# loom-side-panel-left.net
KiCad netlist of a schematic drawn in Altium Designer
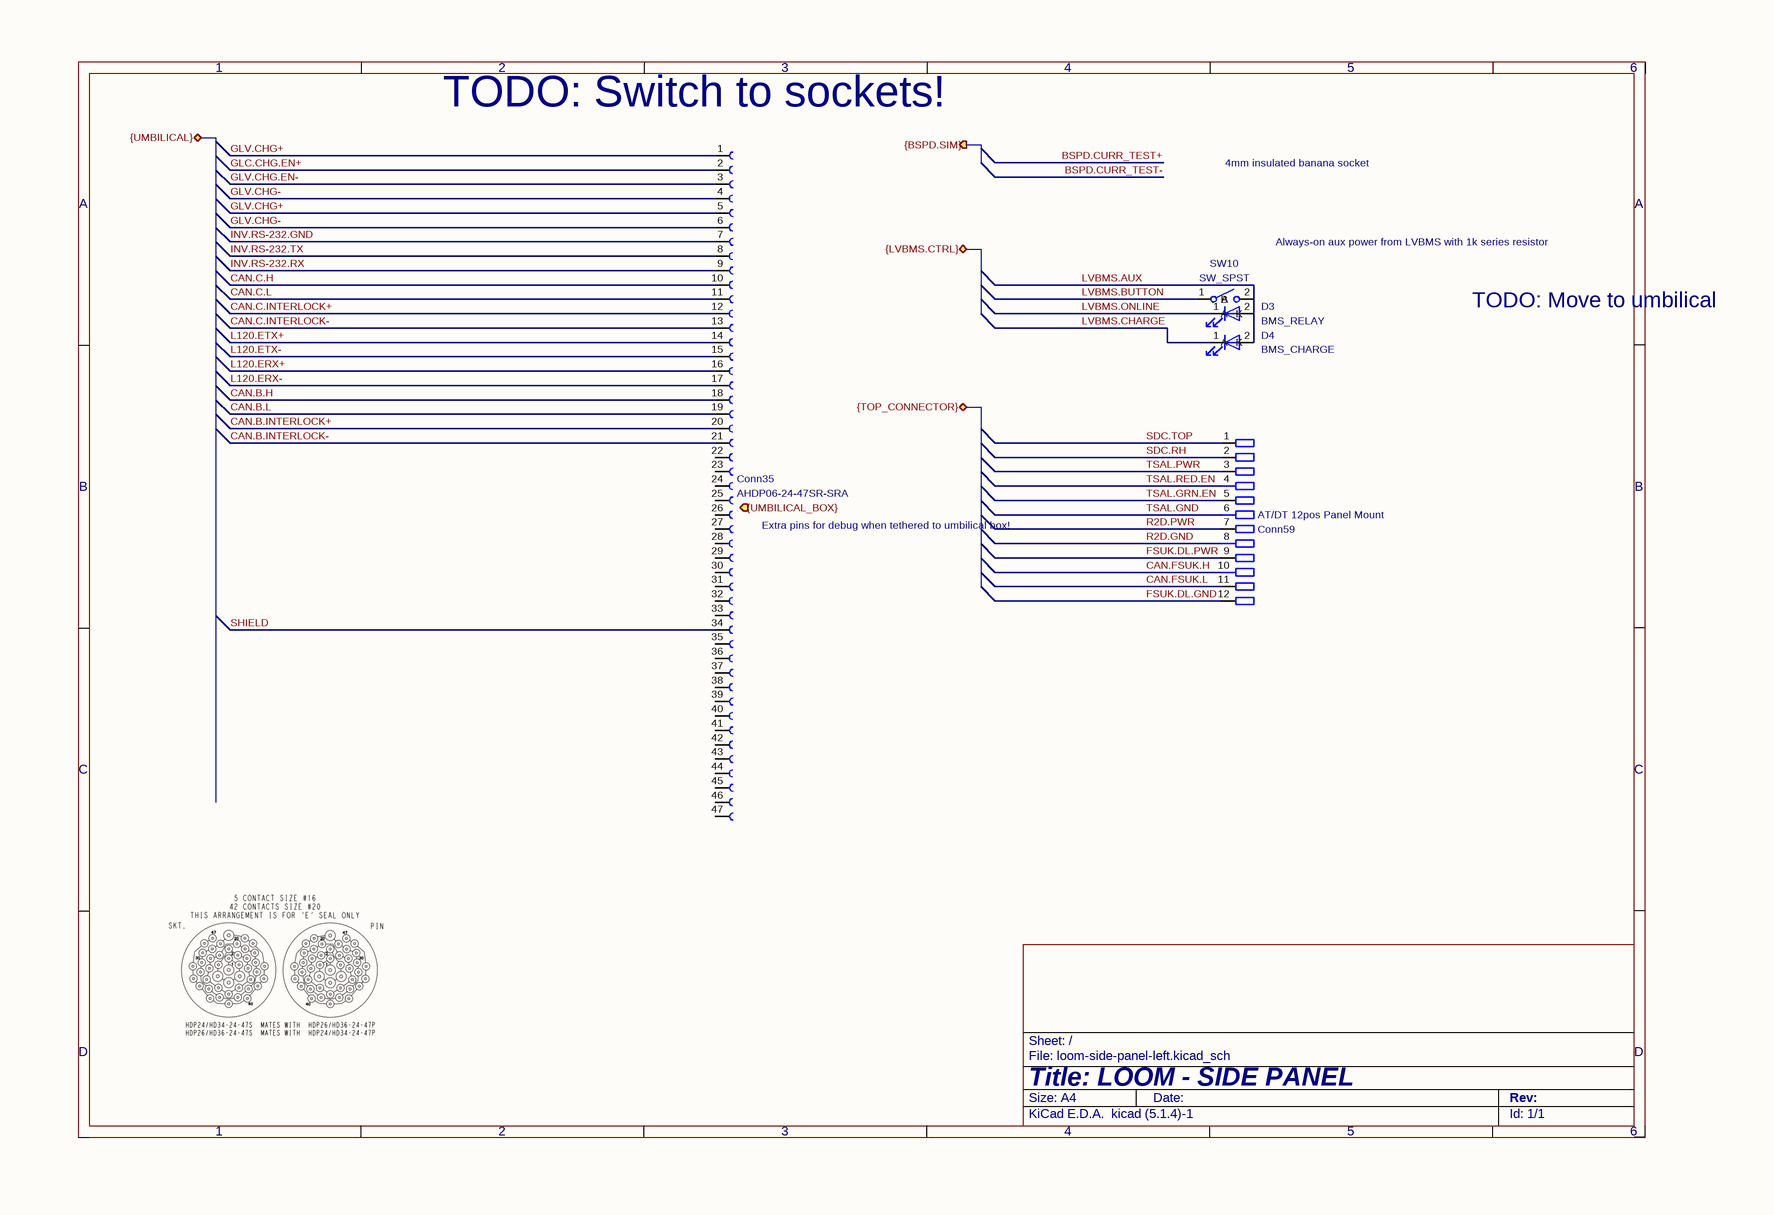
[diagram p0: loom-side-panel-left.SchDoc]

(export (version "E")
  (design (tool "Eeschema 10.0.6"))
  (components
    (comp (ref "Conn35")
      (value "AMPHENOL-47P-Recepticle")
      (fields (field (name "P/N") "AHDP06-24-47SR-SRA"))
      (libsource (lib "Connectors_SUFST") (part "AMPHENOL-47P-Recepticle"))
    )
    (comp (ref "Conn59")
      (value "AMPHENOL-21P-Pannel")
      (fields (field (name "P/N") "AT/DT 12pos Panel Mount"))
      (libsource (lib "Connectors_SUFST") (part "Deutsch_DTM_12P_Pin"))
    )
    (comp (ref "D3")
      (value "BMS_RELAY")
      (description "Light emitting diode")
      (libsource (lib "Device") (part "LED"))
    )
    (comp (ref "D4")
      (value "BMS_CHARGE")
      (description "Light emitting diode")
      (libsource (lib "Device") (part "LED"))
    )
    (comp (ref "SW10")
      (value "SW_SPST")
      (description "Single Pole Single Throw (SPST) switch")
      (libsource (lib "Switch") (part "SW_SPST"))
    )
  )
  (nets
    (net (code "8") (name "/CAN.B.H") (class "Default")
      (node (ref "Conn35") (pin "18") (pinfunction "18_18") (pintype "passive"))
    )
    (net (code "9") (name "/CAN.B.INTERLOCK+") (class "Default")
      (node (ref "Conn35") (pin "20") (pinfunction "20_20") (pintype "passive"))
    )
    (net (code "10") (name "/CAN.B.INTERLOCK-") (class "Default")
      (node (ref "Conn35") (pin "21") (pinfunction "21_21") (pintype "passive"))
    )
    (net (code "11") (name "/CAN.B.L") (class "Default")
      (node (ref "Conn35") (pin "19") (pinfunction "19_19") (pintype "passive"))
    )
    (net (code "12") (name "/CAN.C.H") (class "Default")
      (node (ref "Conn35") (pin "10") (pinfunction "10_10") (pintype "passive"))
    )
    (net (code "13") (name "/CAN.C.INTERLOCK+") (class "Default")
      (node (ref "Conn35") (pin "12") (pinfunction "12_12") (pintype "passive"))
    )
    (net (code "14") (name "/CAN.C.INTERLOCK-") (class "Default")
      (node (ref "Conn35") (pin "13") (pinfunction "13_13") (pintype "passive"))
    )
    (net (code "15") (name "/CAN.C.L") (class "Default")
      (node (ref "Conn35") (pin "11") (pinfunction "11_11") (pintype "passive"))
    )
    (net (code "16") (name "/CAN.FSUK.H") (class "Default")
      (node (ref "Conn59") (pin "10") (pinfunction "10_10") (pintype "passive"))
    )
    (net (code "17") (name "/CAN.FSUK.L") (class "Default")
      (node (ref "Conn59") (pin "11") (pinfunction "11_11") (pintype "passive"))
    )
    (net (code "18") (name "/FSUK.DL.GND") (class "Default")
      (node (ref "Conn59") (pin "12") (pinfunction "12_12") (pintype "passive"))
    )
    (net (code "19") (name "/FSUK.DL.PWR") (class "Default")
      (node (ref "Conn59") (pin "9") (pinfunction "9_9") (pintype "passive"))
    )
    (net (code "20") (name "/GLC.CHG.EN+") (class "Default")
      (node (ref "Conn35") (pin "2") (pinfunction "2_2") (pintype "passive"))
    )
    (net (code "21") (name "/GLV.CHG+") (class "Default")
      (node (ref "Conn35") (pin "1") (pinfunction "1_1") (pintype "passive"))
      (node (ref "Conn35") (pin "5") (pinfunction "5_5") (pintype "passive"))
    )
    (net (code "22") (name "/GLV.CHG-") (class "Default")
      (node (ref "Conn35") (pin "4") (pinfunction "4_4") (pintype "passive"))
      (node (ref "Conn35") (pin "6") (pinfunction "6_6") (pintype "passive"))
    )
    (net (code "23") (name "/GLV.CHG.EN-") (class "Default")
      (node (ref "Conn35") (pin "3") (pinfunction "3_3") (pintype "passive"))
    )
    (net (code "24") (name "/INV.RS-232.GND") (class "Default")
      (node (ref "Conn35") (pin "7") (pinfunction "7_7") (pintype "passive"))
    )
    (net (code "25") (name "/INV.RS-232.RX") (class "Default")
      (node (ref "Conn35") (pin "9") (pinfunction "9_9") (pintype "passive"))
    )
    (net (code "26") (name "/INV.RS-232.TX") (class "Default")
      (node (ref "Conn35") (pin "8") (pinfunction "8_8") (pintype "passive"))
    )
    (net (code "27") (name "/L120.ERX+") (class "Default")
      (node (ref "Conn35") (pin "16") (pinfunction "16_16") (pintype "passive"))
    )
    (net (code "28") (name "/L120.ERX-") (class "Default")
      (node (ref "Conn35") (pin "17") (pinfunction "17_17") (pintype "passive"))
    )
    (net (code "29") (name "/L120.ETX+") (class "Default")
      (node (ref "Conn35") (pin "14") (pinfunction "14_14") (pintype "passive"))
    )
    (net (code "30") (name "/L120.ETX-") (class "Default")
      (node (ref "Conn35") (pin "15") (pinfunction "15_15") (pintype "passive"))
    )
    (net (code "31") (name "/LVBMS.AUX") (class "Default")
      (node (ref "D3") (pin "2") (pinfunction "A_2") (pintype "passive"))
      (node (ref "D4") (pin "2") (pinfunction "A_2") (pintype "passive"))
      (node (ref "SW10") (pin "2") (pinfunction "B_2") (pintype "passive"))
    )
    (net (code "32") (name "/LVBMS.BUTTON") (class "Default")
      (node (ref "SW10") (pin "1") (pinfunction "A_1") (pintype "passive"))
    )
    (net (code "33") (name "/LVBMS.CHARGE") (class "Default")
      (node (ref "D4") (pin "1") (pinfunction "K_1") (pintype "passive"))
    )
    (net (code "34") (name "/LVBMS.ONLINE") (class "Default")
      (node (ref "D3") (pin "1") (pinfunction "K_1") (pintype "passive"))
    )
    (net (code "35") (name "/R2D.GND") (class "Default")
      (node (ref "Conn59") (pin "8") (pinfunction "8_8") (pintype "passive"))
    )
    (net (code "36") (name "/R2D.PWR") (class "Default")
      (node (ref "Conn59") (pin "7") (pinfunction "7_7") (pintype "passive"))
    )
    (net (code "37") (name "/SDC.RH") (class "Default")
      (node (ref "Conn59") (pin "2") (pinfunction "2_2") (pintype "passive"))
    )
    (net (code "38") (name "/SDC.TOP") (class "Default")
      (node (ref "Conn59") (pin "1") (pinfunction "1_1") (pintype "passive"))
    )
    (net (code "39") (name "/SHIELD") (class "Default")
      (node (ref "Conn35") (pin "34") (pinfunction "34_34") (pintype "passive"))
    )
    (net (code "40") (name "/TSAL.GND") (class "Default")
      (node (ref "Conn59") (pin "6") (pinfunction "6_6") (pintype "passive"))
    )
    (net (code "41") (name "/TSAL.GRN.EN") (class "Default")
      (node (ref "Conn59") (pin "5") (pinfunction "5_5") (pintype "passive"))
    )
    (net (code "42") (name "/TSAL.PWR") (class "Default")
      (node (ref "Conn59") (pin "3") (pinfunction "3_3") (pintype "passive"))
    )
    (net (code "43") (name "/TSAL.RED.EN") (class "Default")
      (node (ref "Conn59") (pin "4") (pinfunction "4_4") (pintype "passive"))
    )
    (net (code "49") (name "unconnected-(Conn35-Pad22)") (class "Default")
      (node (ref "Conn35") (pin "22") (pinfunction "22_22") (pintype "passive"))
    )
    (net (code "50") (name "unconnected-(Conn35-Pad23)") (class "Default")
      (node (ref "Conn35") (pin "23") (pinfunction "23_23") (pintype "passive"))
    )
    (net (code "51") (name "unconnected-(Conn35-Pad24)") (class "Default")
      (node (ref "Conn35") (pin "24") (pinfunction "24_24") (pintype "passive"))
    )
    (net (code "52") (name "unconnected-(Conn35-Pad25)") (class "Default")
      (node (ref "Conn35") (pin "25") (pinfunction "25_25") (pintype "passive"))
    )
    (net (code "53") (name "unconnected-(Conn35-Pad26)") (class "Default")
      (node (ref "Conn35") (pin "26") (pinfunction "26_26") (pintype "passive"))
    )
    (net (code "54") (name "unconnected-(Conn35-Pad27)") (class "Default")
      (node (ref "Conn35") (pin "27") (pinfunction "27_27") (pintype "passive"))
    )
    (net (code "55") (name "unconnected-(Conn35-Pad28)") (class "Default")
      (node (ref "Conn35") (pin "28") (pinfunction "28_28") (pintype "passive"))
    )
    (net (code "56") (name "unconnected-(Conn35-Pad29)") (class "Default")
      (node (ref "Conn35") (pin "29") (pinfunction "29_29") (pintype "passive"))
    )
    (net (code "57") (name "unconnected-(Conn35-Pad30)") (class "Default")
      (node (ref "Conn35") (pin "30") (pinfunction "30_30") (pintype "passive"))
    )
    (net (code "58") (name "unconnected-(Conn35-Pad31)") (class "Default")
      (node (ref "Conn35") (pin "31") (pinfunction "31_31") (pintype "passive"))
    )
    (net (code "59") (name "unconnected-(Conn35-Pad32)") (class "Default")
      (node (ref "Conn35") (pin "32") (pinfunction "32_32") (pintype "passive"))
    )
    (net (code "60") (name "unconnected-(Conn35-Pad33)") (class "Default")
      (node (ref "Conn35") (pin "33") (pinfunction "33_33") (pintype "passive"))
    )
    (net (code "61") (name "unconnected-(Conn35-Pad35)") (class "Default")
      (node (ref "Conn35") (pin "35") (pinfunction "35_35") (pintype "passive"))
    )
    (net (code "62") (name "unconnected-(Conn35-Pad36)") (class "Default")
      (node (ref "Conn35") (pin "36") (pinfunction "36_36") (pintype "passive"))
    )
    (net (code "63") (name "unconnected-(Conn35-Pad37)") (class "Default")
      (node (ref "Conn35") (pin "37") (pinfunction "37_37") (pintype "passive"))
    )
    (net (code "64") (name "unconnected-(Conn35-Pad38)") (class "Default")
      (node (ref "Conn35") (pin "38") (pinfunction "38_38") (pintype "passive"))
    )
    (net (code "65") (name "unconnected-(Conn35-Pad39)") (class "Default")
      (node (ref "Conn35") (pin "39") (pinfunction "39_39") (pintype "passive"))
    )
    (net (code "66") (name "unconnected-(Conn35-Pad40)") (class "Default")
      (node (ref "Conn35") (pin "40") (pinfunction "40_40") (pintype "passive"))
    )
    (net (code "67") (name "unconnected-(Conn35-Pad41)") (class "Default")
      (node (ref "Conn35") (pin "41") (pinfunction "41_41") (pintype "passive"))
    )
    (net (code "68") (name "unconnected-(Conn35-Pad42)") (class "Default")
      (node (ref "Conn35") (pin "42") (pinfunction "42_42") (pintype "passive"))
    )
    (net (code "69") (name "unconnected-(Conn35-Pad43)") (class "Default")
      (node (ref "Conn35") (pin "43") (pinfunction "43_43") (pintype "passive"))
    )
    (net (code "70") (name "unconnected-(Conn35-Pad44)") (class "Default")
      (node (ref "Conn35") (pin "44") (pinfunction "44_44") (pintype "passive"))
    )
    (net (code "71") (name "unconnected-(Conn35-Pad45)") (class "Default")
      (node (ref "Conn35") (pin "45") (pinfunction "45_45") (pintype "passive"))
    )
    (net (code "72") (name "unconnected-(Conn35-Pad46)") (class "Default")
      (node (ref "Conn35") (pin "46") (pinfunction "46_46") (pintype "passive"))
    )
    (net (code "73") (name "unconnected-(Conn35-Pad47)") (class "Default")
      (node (ref "Conn35") (pin "47") (pinfunction "47_47") (pintype "passive"))
    )
  )
)
